# stepperMotorDriver.net
KiCad netlist of a schematic drawn in Altium Designer
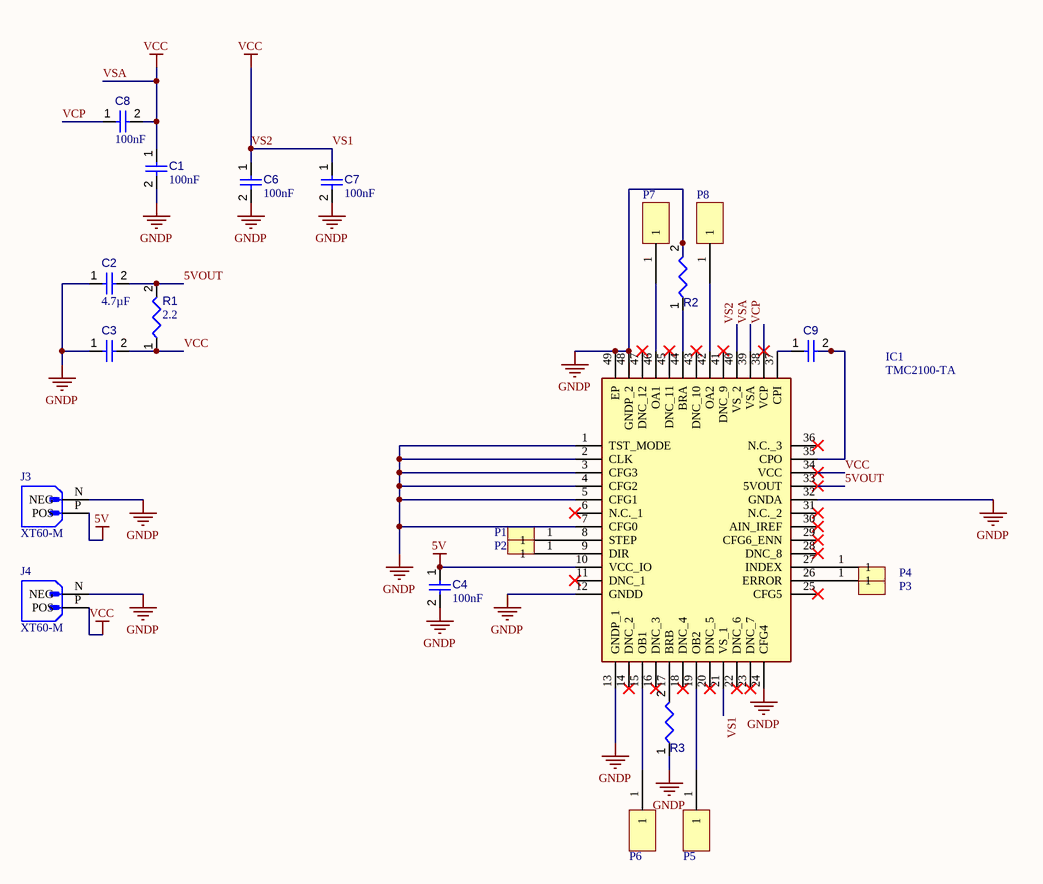
[diagram p0: stepperMotorDriver.SchDoc]

(export (version "E")
  (design (tool "Eeschema 10.0.6"))
  (components
    (comp (ref "C1")
      (value "100nF")
      (footprint "FP-0805-L_2_01_0_2-W_1_25-IPC_B")
      (fields (field (name "Comment") "08055C104J4T2A"))
      (libsource (lib "CPRT Workspace") (part "CAP-NP-2"))
    )
    (comp (ref "C2")
      (value "4.7µF")
      (footprint "CAPC0805(2012)145_L")
      (description "Chip Capacitor, 4.7µF +/-40%, 25V, 0805, Thickness 1.45 mm")
      (fields (field (name "TOLERANCE") "20%") (field (name "Comment") "Capacitor 4.7µF +/-40% 25V 0805"))
      (libsource (lib "CPRT Workspace") (part "CAP-NP-2"))
    )
    (comp (ref "C3")
      (value "Capacitor 4.7µF +/-40% 25V 0805")
      (footprint "CAPC0805(2012)145_L")
      (description "Chip Capacitor, 4.7µF +/-40%, 25V, 0805, Thickness 1.45 mm")
      (fields (field (name "TOLERANCE") "20%"))
      (libsource (lib "CPRT Workspace") (part "CAP-NP-2"))
    )
    (comp (ref "C4")
      (value "100nF")
      (footprint "FP-0805-L_2_01_0_2-W_1_25-IPC_B")
      (fields (field (name "Comment") "08055C104J4T2A"))
      (libsource (lib "CPRT Workspace") (part "CAP-NP-2"))
    )
    (comp (ref "C6")
      (value "100nF")
      (footprint "FP-0805-L_2_01_0_2-W_1_25-IPC_B")
      (fields (field (name "Comment") "08055C104J4T2A"))
      (libsource (lib "CPRT Workspace") (part "CAP-NP-2"))
    )
    (comp (ref "C7")
      (value "100nF")
      (footprint "FP-0805-L_2_01_0_2-W_1_25-IPC_B")
      (fields (field (name "Comment") "08055C104J4T2A"))
      (libsource (lib "CPRT Workspace") (part "CAP-NP-2"))
    )
    (comp (ref "C8")
      (value "100nF")
      (footprint "FP-0805-L_2_01_0_2-W_1_25-IPC_B")
      (fields (field (name "Comment") "08055C104J4T2A"))
      (libsource (lib "CPRT Workspace") (part "CAP-NP-2"))
    )
    (comp (ref "C9")
      (value "08055C104J4T2A")
      (footprint "FP-0805-L_2_01_0_2-W_1_25-IPC_B")
      (libsource (lib "CPRT Workspace") (part "CAP-NP-2"))
    )
    (comp (ref "IC1")
      (value "TMC2100-TA")
      (footprint "SamacSys:QFP50P900X900X120-49N")
      (description "Integrated Circuit")
      (fields (field (name "MOUSER PART NUMBER") "700-TMC2100TA"))
      (libsource (lib "*") (part "TMC2100-TA"))
    )
    (comp (ref "J3")
      (value "XT60-M")
      (footprint "AMASS_XT60-M")
      (description "Plug; DC supply; XT60; male; PIN: 2; for cable; soldered; 30A; 500V")
      (fields (field (name "MF") "AMASS"))
      (libsource (lib "CPRT Workspace") (part "XT60-M"))
    )
    (comp (ref "J4")
      (value "XT60-M")
      (footprint "AMASS_XT60-M")
      (description "Plug; DC supply; XT60; male; PIN: 2; for cable; soldered; 30A; 500V")
      (fields (field (name "MF") "AMASS"))
      (libsource (lib "CPRT Workspace") (part "XT60-M"))
    )
    (comp (ref "P1")
      (value "P")
      (footprint "Pad 2mm x 5mm-Footprint-1")
      (description "a 2.5mm by 5mm copper pad")
      (libsource (lib "CPRT Workspace") (part "Pad 2mm x 5mm-Symbol-1"))
    )
    (comp (ref "P2")
      (value "Pad 2mm5x 5mm")
      (footprint "Pad 2mm x 5mm-Footprint-1")
      (description "a 2.5mm by 5mm copper pad")
      (libsource (lib "CPRT Workspace") (part "Pad 2mm x 5mm-Symbol-1"))
    )
    (comp (ref "P3")
      (value "Pad 2mm5x 5mm")
      (footprint "Pad 2mm x 5mm-Footprint-1")
      (description "a 2.5mm by 5mm copper pad")
      (libsource (lib "") (part "Pad 2mm x 5mm-Symbol-1_1"))
    )
    (comp (ref "P4")
      (value "Pad 2mm5x 5mm")
      (footprint "Pad 2mm x 5mm-Footprint-1")
      (description "a 2.5mm by 5mm copper pad")
      (libsource (lib "") (part "Pad 2mm x 5mm-Symbol-1_1"))
    )
    (comp (ref "P5")
      (value "Pad 3mm5 by 5mm")
      (footprint "Pad 3mm5 by 5mm-Footprint-1")
      (description "a 3.5mm by 5mm pad")
      (libsource (lib "") (part "Pad 3mm5 by 5mm-Symbol-1_1"))
    )
    (comp (ref "P6")
      (value "Pad 3mm5 by 5mm")
      (footprint "Pad 3mm5 by 5mm-Footprint-1")
      (description "a 3.5mm by 5mm pad")
      (libsource (lib "") (part "Pad 3mm5 by 5mm-Symbol-1_1"))
    )
    (comp (ref "P7")
      (value "Pad 3mm5 by 5mm")
      (footprint "Pad 3mm5 by 5mm-Footprint-1")
      (description "a 3.5mm by 5mm pad")
      (libsource (lib "CPRT Workspace") (part "Pad 3mm5 by 5mm-Symbol-1"))
    )
    (comp (ref "P8")
      (value "Pad 3mm5 by 5mm")
      (footprint "Pad 3mm5 by 5mm-Footprint-1")
      (description "a 3.5mm by 5mm pad")
      (libsource (lib "CPRT Workspace") (part "Pad 3mm5 by 5mm-Symbol-1"))
    )
    (comp (ref "R1")
      (value "2.2")
      (footprint "RESC0402(1005)_L")
      (description "Chip Resistor, 2,2 Ohms, +/-5 %, 63 mW, -55 to 155 degC, 0402")
      (fields (field (name "POWER") "63mW") (field (name "TOLERANCE") "5%"))
      (libsource (lib "CPRT Workspace") (part "RES-2"))
    )
    (comp (ref "R2")
      (value "Resistor 470R +/-5% 0805 125 mW")
      (footprint "RESC0805(2012)_L")
      (description "Chip Resistor, 470 Ohms, +/-5%, 125 mW, -55 to 155 degC, 0805")
      (fields (field (name "TOLERANCE") "5%") (field (name "POWER") "125mW"))
      (libsource (lib "CPRT Workspace") (part "RES-2"))
    )
    (comp (ref "R3")
      (value "Resistor 470R +/-5% 0805 125 mW")
      (footprint "RESC0805(2012)_L")
      (description "Chip Resistor, 470 Ohms, +/-5%, 125 mW, -55 to 155 degC, 0805")
      (fields (field (name "TOLERANCE") "5%") (field (name "POWER") "125mW"))
      (libsource (lib "CPRT Workspace") (part "RES-2"))
    )
  )
  (nets
    (net (code "1") (name "/5VOUT") (class "Default")
      (node (ref "C2") (pin "2") (pinfunction "2_2") (pintype "passive"))
      (node (ref "IC1") (pin "33") (pinfunction "5VOUT_33") (pintype "passive"))
      (node (ref "R1") (pin "2") (pinfunction "2_2") (pintype "passive"))
    )
    (net (code "2") (name "/VCP") (class "Default")
      (node (ref "C8") (pin "1") (pinfunction "1_1") (pintype "passive"))
      (node (ref "IC1") (pin "38") (pinfunction "VCP_38") (pintype "passive"))
    )
    (net (code "3") (name "5V") (class "Default")
      (node (ref "C4") (pin "1") (pinfunction "1_1") (pintype "passive"))
      (node (ref "IC1") (pin "10") (pinfunction "VCC_IO_10") (pintype "passive"))
      (node (ref "J3") (pin "P") (pinfunction "POS_P") (pintype "passive"))
    )
    (net (code "4") (name "GNDP") (class "Default")
      (node (ref "C1") (pin "2") (pinfunction "2_2") (pintype "passive"))
      (node (ref "C2") (pin "1") (pinfunction "1_1") (pintype "passive"))
      (node (ref "C3") (pin "1") (pinfunction "1_1") (pintype "passive"))
      (node (ref "C4") (pin "2") (pinfunction "2_2") (pintype "passive"))
      (node (ref "C6") (pin "2") (pinfunction "2_2") (pintype "passive"))
      (node (ref "C7") (pin "2") (pinfunction "2_2") (pintype "passive"))
      (node (ref "IC1") (pin "1") (pinfunction "TST_MODE_1") (pintype "passive"))
      (node (ref "IC1") (pin "12") (pinfunction "GNDD_12") (pintype "passive"))
      (node (ref "IC1") (pin "13") (pinfunction "GNDP_1_13") (pintype "passive"))
      (node (ref "IC1") (pin "2") (pinfunction "CLK_2") (pintype "passive"))
      (node (ref "IC1") (pin "24") (pinfunction "CFG4_24") (pintype "passive"))
      (node (ref "IC1") (pin "3") (pinfunction "CFG3_3") (pintype "passive"))
      (node (ref "IC1") (pin "32") (pinfunction "GNDA_32") (pintype "passive"))
      (node (ref "IC1") (pin "4") (pinfunction "CFG2_4") (pintype "passive"))
      (node (ref "IC1") (pin "48") (pinfunction "GNDP_2_48") (pintype "passive"))
      (node (ref "IC1") (pin "49") (pinfunction "EP_49") (pintype "passive"))
      (node (ref "IC1") (pin "5") (pinfunction "CFG1_5") (pintype "passive"))
      (node (ref "IC1") (pin "7") (pinfunction "CFG0_7") (pintype "passive"))
      (node (ref "J3") (pin "N") (pinfunction "NEG_N") (pintype "passive"))
      (node (ref "J4") (pin "N") (pinfunction "NEG_N") (pintype "passive"))
      (node (ref "R2") (pin "2") (pinfunction "2_2") (pintype "passive"))
      (node (ref "R3") (pin "1") (pinfunction "1_1") (pintype "passive"))
    )
    (net (code "5") (name "Net-(IC1-BRA)") (class "Default")
      (node (ref "IC1") (pin "44") (pinfunction "BRA_44") (pintype "passive"))
      (node (ref "R2") (pin "1") (pinfunction "1_1") (pintype "passive"))
    )
    (net (code "6") (name "Net-(IC1-BRB)") (class "Default")
      (node (ref "IC1") (pin "17") (pinfunction "BRB_17") (pintype "passive"))
      (node (ref "R3") (pin "2") (pinfunction "2_2") (pintype "passive"))
    )
    (net (code "7") (name "Net-(IC1-CPI)") (class "Default")
      (node (ref "C9") (pin "1") (pinfunction "1_1") (pintype "passive"))
      (node (ref "IC1") (pin "37") (pinfunction "CPI_37") (pintype "passive"))
    )
    (net (code "8") (name "Net-(IC1-CPO)") (class "Default")
      (node (ref "C9") (pin "2") (pinfunction "2_2") (pintype "passive"))
      (node (ref "IC1") (pin "35") (pinfunction "CPO_35") (pintype "passive"))
    )
    (net (code "9") (name "Net-(IC1-DIR)") (class "Default")
      (node (ref "IC1") (pin "9") (pinfunction "DIR_9") (pintype "passive"))
      (node (ref "P2") (pin "1") (pinfunction "1_1") (pintype "passive"))
    )
    (net (code "10") (name "Net-(IC1-ERROR)") (class "Default")
      (node (ref "IC1") (pin "26") (pinfunction "ERROR_26") (pintype "passive"))
      (node (ref "P3") (pin "1") (pinfunction "1_1") (pintype "passive"))
    )
    (net (code "11") (name "Net-(IC1-INDEX)") (class "Default")
      (node (ref "IC1") (pin "27") (pinfunction "INDEX_27") (pintype "passive"))
      (node (ref "P4") (pin "1") (pinfunction "1_1") (pintype "passive"))
    )
    (net (code "12") (name "Net-(IC1-OA1)") (class "Default")
      (node (ref "IC1") (pin "46") (pinfunction "OA1_46") (pintype "passive"))
      (node (ref "P7") (pin "1") (pinfunction "1_1") (pintype "passive"))
    )
    (net (code "13") (name "Net-(IC1-OA2)") (class "Default")
      (node (ref "IC1") (pin "42") (pinfunction "OA2_42") (pintype "passive"))
      (node (ref "P8") (pin "1") (pinfunction "1_1") (pintype "passive"))
    )
    (net (code "14") (name "Net-(IC1-OB1)") (class "Default")
      (node (ref "IC1") (pin "15") (pinfunction "OB1_15") (pintype "passive"))
      (node (ref "P6") (pin "1") (pinfunction "1_1") (pintype "passive"))
    )
    (net (code "15") (name "Net-(IC1-OB2)") (class "Default")
      (node (ref "IC1") (pin "19") (pinfunction "OB2_19") (pintype "passive"))
      (node (ref "P5") (pin "1") (pinfunction "1_1") (pintype "passive"))
    )
    (net (code "16") (name "Net-(IC1-STEP)") (class "Default")
      (node (ref "IC1") (pin "8") (pinfunction "STEP_8") (pintype "passive"))
      (node (ref "P1") (pin "1") (pinfunction "1_1") (pintype "passive"))
    )
    (net (code "17") (name "VCC") (class "Default")
      (node (ref "C1") (pin "1") (pinfunction "1_1") (pintype "passive"))
      (node (ref "C3") (pin "2") (pinfunction "2_2") (pintype "passive"))
      (node (ref "C6") (pin "1") (pinfunction "1_1") (pintype "passive"))
      (node (ref "C7") (pin "1") (pinfunction "1_1") (pintype "passive"))
      (node (ref "C8") (pin "2") (pinfunction "2_2") (pintype "passive"))
      (node (ref "IC1") (pin "21") (pinfunction "VS_1_21") (pintype "passive"))
      (node (ref "IC1") (pin "34") (pinfunction "VCC_34") (pintype "passive"))
      (node (ref "IC1") (pin "39") (pinfunction "VSA_39") (pintype "passive"))
      (node (ref "IC1") (pin "40") (pinfunction "VS_2_40") (pintype "passive"))
      (node (ref "J4") (pin "P") (pinfunction "POS_P") (pintype "passive"))
      (node (ref "R1") (pin "1") (pinfunction "1_1") (pintype "passive"))
    )
    (net (code "18") (name "unconnected-(IC1-AIN_IREF-Pad30)") (class "Default")
      (node (ref "IC1") (pin "30") (pinfunction "AIN_IREF_30") (pintype "passive+no_connect"))
    )
    (net (code "19") (name "unconnected-(IC1-CFG5-Pad25)") (class "Default")
      (node (ref "IC1") (pin "25") (pinfunction "CFG5_25") (pintype "passive+no_connect"))
    )
    (net (code "20") (name "unconnected-(IC1-CFG6_ENN-Pad29)") (class "Default")
      (node (ref "IC1") (pin "29") (pinfunction "CFG6_ENN_29") (pintype "passive+no_connect"))
    )
    (net (code "21") (name "unconnected-(IC1-DNC_1-Pad11)") (class "Default")
      (node (ref "IC1") (pin "11") (pinfunction "DNC_1_11") (pintype "passive+no_connect"))
    )
    (net (code "22") (name "unconnected-(IC1-DNC_2-Pad14)") (class "Default")
      (node (ref "IC1") (pin "14") (pinfunction "DNC_2_14") (pintype "passive+no_connect"))
    )
    (net (code "23") (name "unconnected-(IC1-DNC_3-Pad16)") (class "Default")
      (node (ref "IC1") (pin "16") (pinfunction "DNC_3_16") (pintype "passive+no_connect"))
    )
    (net (code "24") (name "unconnected-(IC1-DNC_4-Pad18)") (class "Default")
      (node (ref "IC1") (pin "18") (pinfunction "DNC_4_18") (pintype "passive+no_connect"))
    )
    (net (code "25") (name "unconnected-(IC1-DNC_5-Pad20)") (class "Default")
      (node (ref "IC1") (pin "20") (pinfunction "DNC_5_20") (pintype "passive+no_connect"))
    )
    (net (code "26") (name "unconnected-(IC1-DNC_6-Pad22)") (class "Default")
      (node (ref "IC1") (pin "22") (pinfunction "DNC_6_22") (pintype "passive+no_connect"))
    )
    (net (code "27") (name "unconnected-(IC1-DNC_7-Pad23)") (class "Default")
      (node (ref "IC1") (pin "23") (pinfunction "DNC_7_23") (pintype "passive+no_connect"))
    )
    (net (code "28") (name "unconnected-(IC1-DNC_8-Pad28)") (class "Default")
      (node (ref "IC1") (pin "28") (pinfunction "DNC_8_28") (pintype "passive+no_connect"))
    )
    (net (code "29") (name "unconnected-(IC1-DNC_9-Pad41)") (class "Default")
      (node (ref "IC1") (pin "41") (pinfunction "DNC_9_41") (pintype "passive+no_connect"))
    )
    (net (code "30") (name "unconnected-(IC1-DNC_10-Pad43)") (class "Default")
      (node (ref "IC1") (pin "43") (pinfunction "DNC_10_43") (pintype "passive+no_connect"))
    )
    (net (code "31") (name "unconnected-(IC1-DNC_11-Pad45)") (class "Default")
      (node (ref "IC1") (pin "45") (pinfunction "DNC_11_45") (pintype "passive+no_connect"))
    )
    (net (code "32") (name "unconnected-(IC1-DNC_12-Pad47)") (class "Default")
      (node (ref "IC1") (pin "47") (pinfunction "DNC_12_47") (pintype "passive+no_connect"))
    )
    (net (code "33") (name "unconnected-(IC1-N.C._1-Pad6)") (class "Default")
      (node (ref "IC1") (pin "6") (pinfunction "N.C._1_6") (pintype "passive+no_connect"))
    )
    (net (code "34") (name "unconnected-(IC1-N.C._2-Pad31)") (class "Default")
      (node (ref "IC1") (pin "31") (pinfunction "N.C._2_31") (pintype "passive+no_connect"))
    )
    (net (code "35") (name "unconnected-(IC1-N.C._3-Pad36)") (class "Default")
      (node (ref "IC1") (pin "36") (pinfunction "N.C._3_36") (pintype "passive+no_connect"))
    )
  )
)
